# schematic.net
KiCad netlist of a schematic drawn in EasyEDA
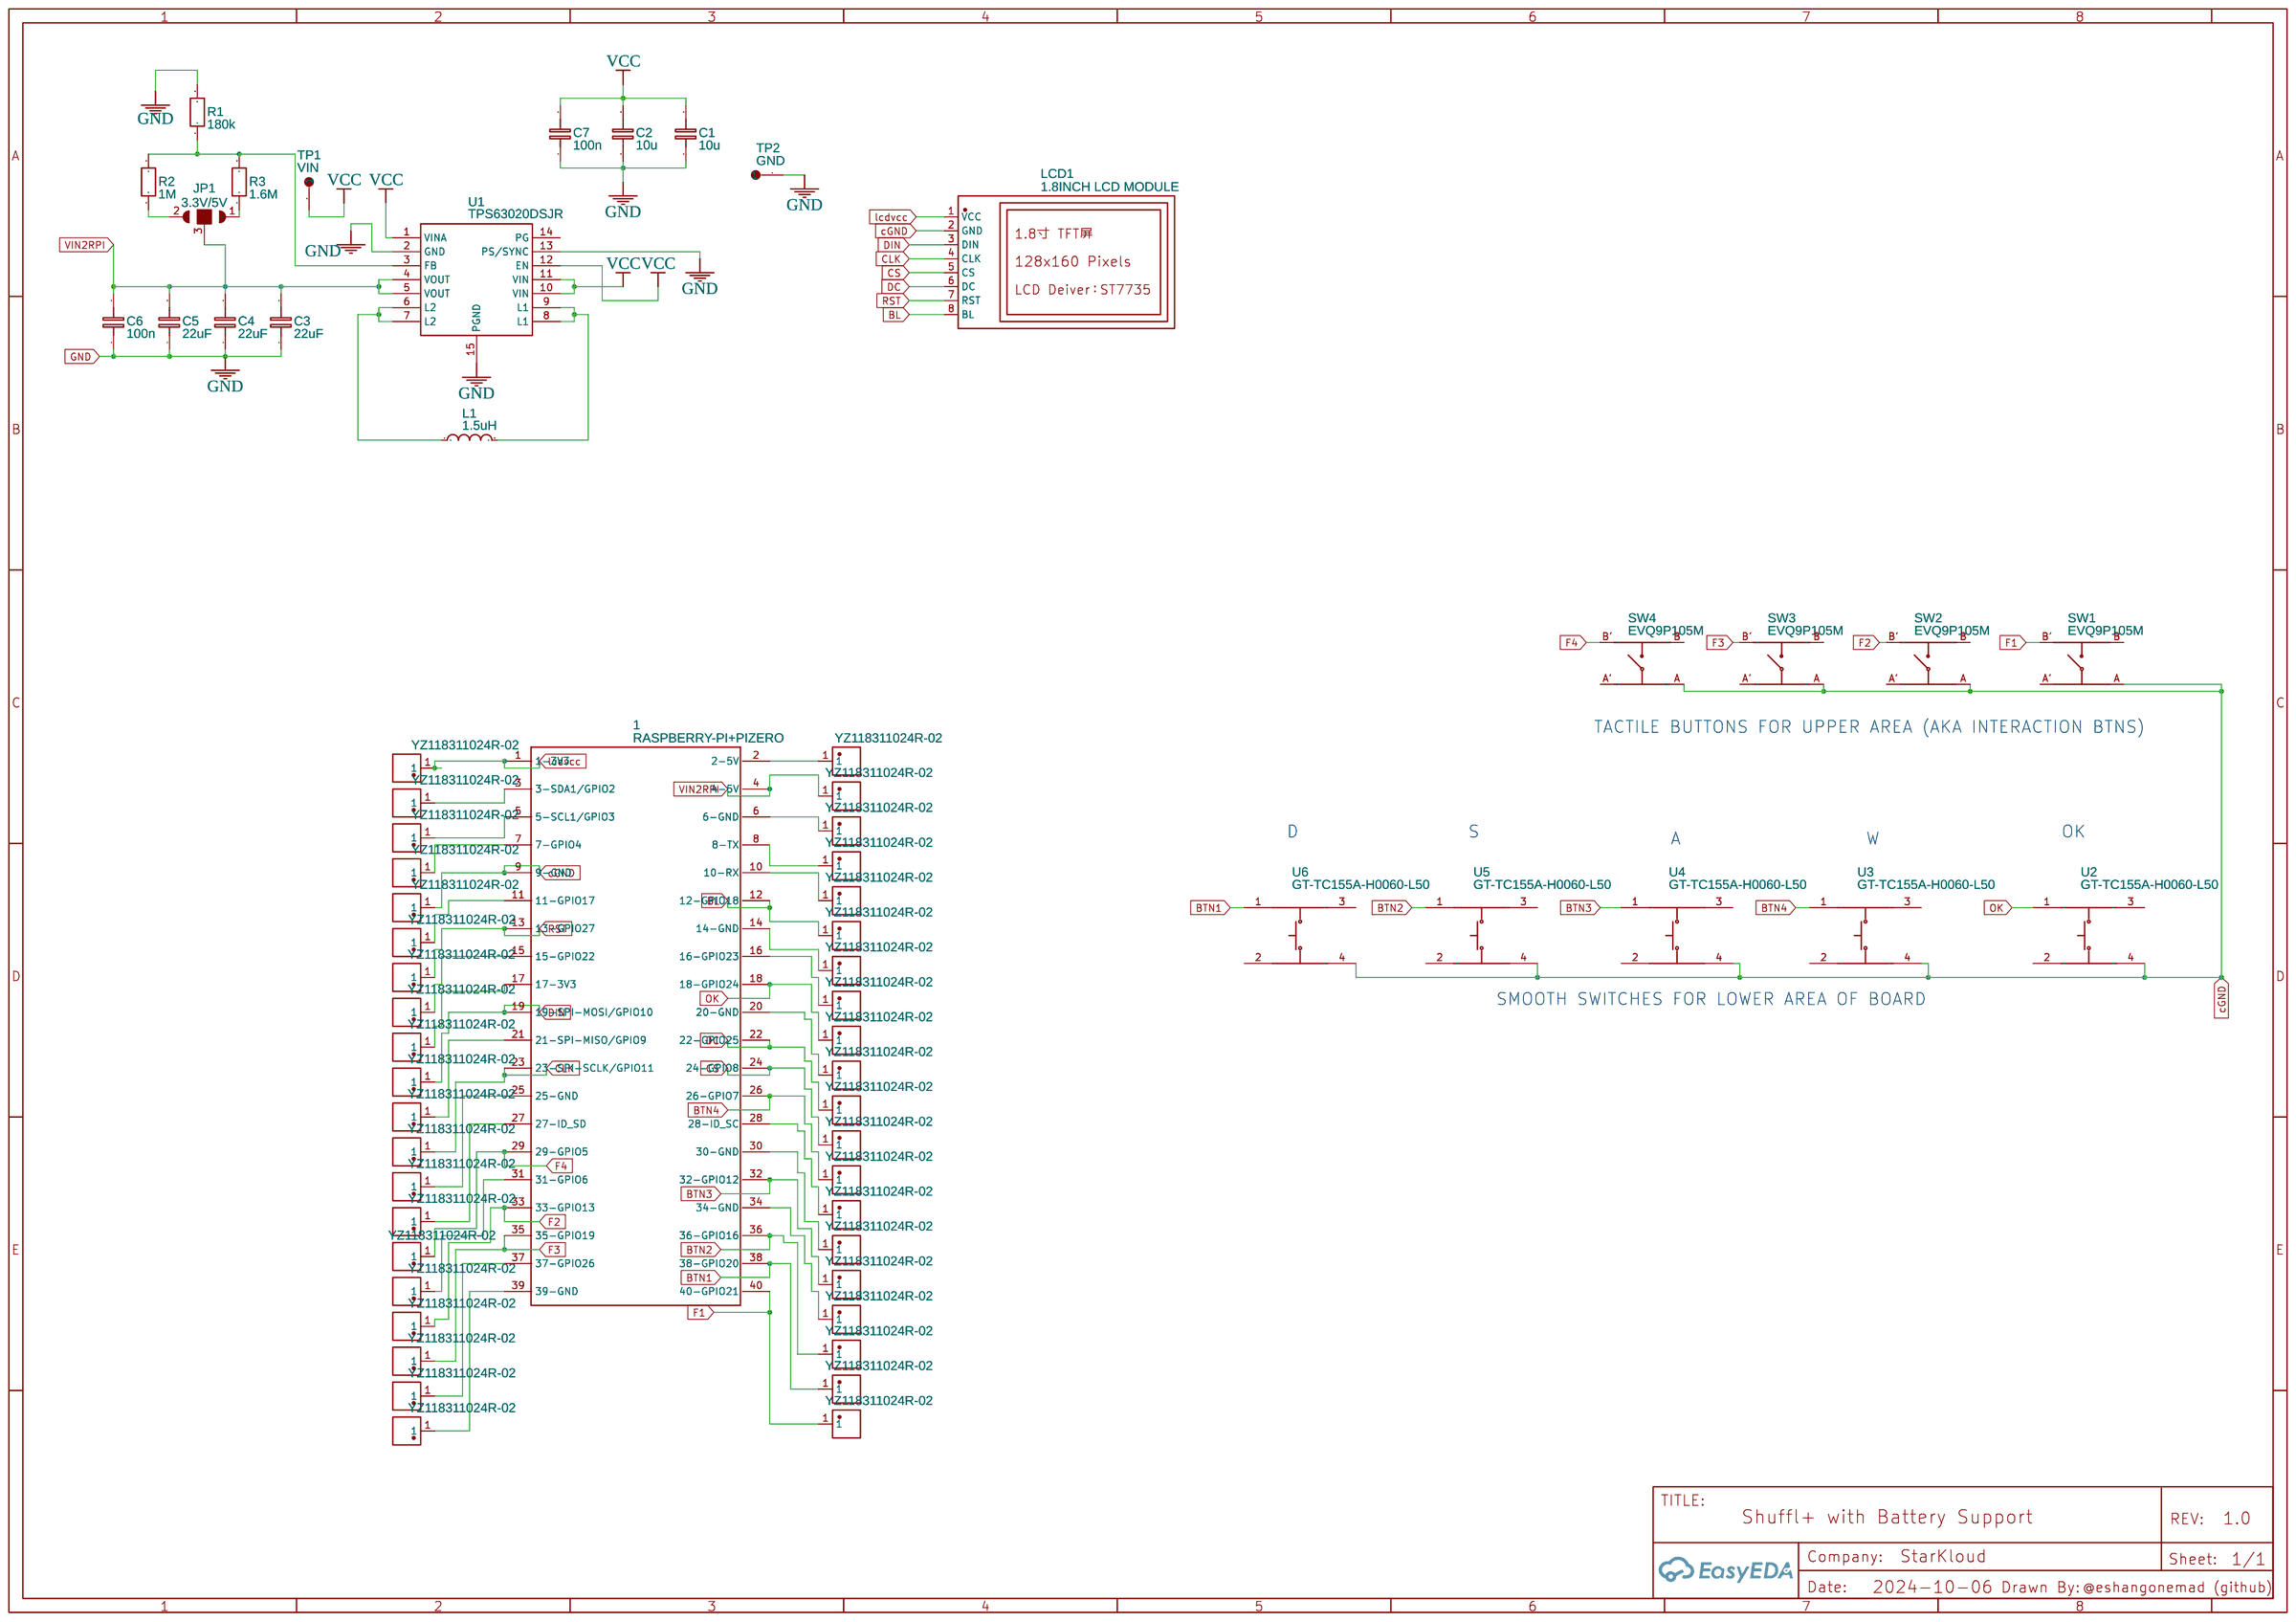
[diagram p0: schematic sheet]

(export (version "E")
  (design (tool "Eeschema 10.0.6"))
  (components
    (comp (ref "1") (value "RASPBERRY-PI+PIZERO") (libsource (lib "") (part "RASPBERRY-PI+PIZERO")))
    (comp (ref "2")
      (value "YZ118311024R-02")
      (fields (field (name "Manufacturer") "Xinyangze(鑫扬泽)"))
      (libsource (lib "") (part "YZ118311024R-02"))
    )
    (comp (ref "3")
      (value "YZ118311024R-02")
      (fields (field (name "Manufacturer") "Xinyangze(鑫扬泽)"))
      (libsource (lib "") (part "YZ118311024R-02_1"))
    )
    (comp (ref "4")
      (value "YZ118311024R-02")
      (fields (field (name "Manufacturer") "Xinyangze(鑫扬泽)"))
      (libsource (lib "") (part "YZ118311024R-02"))
    )
    (comp (ref "5")
      (value "YZ118311024R-02")
      (fields (field (name "Manufacturer") "Xinyangze(鑫扬泽)"))
      (libsource (lib "") (part "YZ118311024R-02_1"))
    )
    (comp (ref "6")
      (value "YZ118311024R-02")
      (fields (field (name "Manufacturer") "Xinyangze(鑫扬泽)"))
      (libsource (lib "") (part "YZ118311024R-02"))
    )
    (comp (ref "7")
      (value "YZ118311024R-02")
      (fields (field (name "Manufacturer") "Xinyangze(鑫扬泽)"))
      (libsource (lib "") (part "YZ118311024R-02_1"))
    )
    (comp (ref "8")
      (value "YZ118311024R-02")
      (fields (field (name "Manufacturer") "Xinyangze(鑫扬泽)"))
      (libsource (lib "") (part "YZ118311024R-02"))
    )
    (comp (ref "9")
      (value "YZ118311024R-02")
      (fields (field (name "Manufacturer") "Xinyangze(鑫扬泽)"))
      (libsource (lib "") (part "YZ118311024R-02_1"))
    )
    (comp (ref "10")
      (value "YZ118311024R-02")
      (fields (field (name "Manufacturer") "Xinyangze(鑫扬泽)"))
      (libsource (lib "") (part "YZ118311024R-02"))
    )
    (comp (ref "11")
      (value "YZ118311024R-02")
      (fields (field (name "Manufacturer") "Xinyangze(鑫扬泽)"))
      (libsource (lib "") (part "YZ118311024R-02_1"))
    )
    (comp (ref "12")
      (value "YZ118311024R-02")
      (fields (field (name "Manufacturer") "Xinyangze(鑫扬泽)"))
      (libsource (lib "") (part "YZ118311024R-02"))
    )
    (comp (ref "13")
      (value "YZ118311024R-02")
      (fields (field (name "Manufacturer") "Xinyangze(鑫扬泽)"))
      (libsource (lib "") (part "YZ118311024R-02_1"))
    )
    (comp (ref "14")
      (value "YZ118311024R-02")
      (fields (field (name "Manufacturer") "Xinyangze(鑫扬泽)"))
      (libsource (lib "") (part "YZ118311024R-02"))
    )
    (comp (ref "15")
      (value "YZ118311024R-02")
      (fields (field (name "Manufacturer") "Xinyangze(鑫扬泽)"))
      (libsource (lib "") (part "YZ118311024R-02_1"))
    )
    (comp (ref "16")
      (value "YZ118311024R-02")
      (fields (field (name "Manufacturer") "Xinyangze(鑫扬泽)"))
      (libsource (lib "") (part "YZ118311024R-02"))
    )
    (comp (ref "17")
      (value "YZ118311024R-02")
      (fields (field (name "Manufacturer") "Xinyangze(鑫扬泽)"))
      (libsource (lib "") (part "YZ118311024R-02_1"))
    )
    (comp (ref "18")
      (value "YZ118311024R-02")
      (fields (field (name "Manufacturer") "Xinyangze(鑫扬泽)"))
      (libsource (lib "") (part "YZ118311024R-02"))
    )
    (comp (ref "19")
      (value "YZ118311024R-02")
      (fields (field (name "Manufacturer") "Xinyangze(鑫扬泽)"))
      (libsource (lib "") (part "YZ118311024R-02_1"))
    )
    (comp (ref "20")
      (value "YZ118311024R-02")
      (fields (field (name "Manufacturer") "Xinyangze(鑫扬泽)"))
      (libsource (lib "") (part "YZ118311024R-02"))
    )
    (comp (ref "21")
      (value "YZ118311024R-02")
      (fields (field (name "Manufacturer") "Xinyangze(鑫扬泽)"))
      (libsource (lib "") (part "YZ118311024R-02_1"))
    )
    (comp (ref "22")
      (value "YZ118311024R-02")
      (fields (field (name "Manufacturer") "Xinyangze(鑫扬泽)"))
      (libsource (lib "") (part "YZ118311024R-02"))
    )
    (comp (ref "23")
      (value "YZ118311024R-02")
      (fields (field (name "Manufacturer") "Xinyangze(鑫扬泽)"))
      (libsource (lib "") (part "YZ118311024R-02_1"))
    )
    (comp (ref "24")
      (value "YZ118311024R-02")
      (fields (field (name "Manufacturer") "Xinyangze(鑫扬泽)"))
      (libsource (lib "") (part "YZ118311024R-02"))
    )
    (comp (ref "25")
      (value "YZ118311024R-02")
      (fields (field (name "Manufacturer") "Xinyangze(鑫扬泽)"))
      (libsource (lib "") (part "YZ118311024R-02_1"))
    )
    (comp (ref "26")
      (value "YZ118311024R-02")
      (fields (field (name "Manufacturer") "Xinyangze(鑫扬泽)"))
      (libsource (lib "") (part "YZ118311024R-02"))
    )
    (comp (ref "27")
      (value "YZ118311024R-02")
      (fields (field (name "Manufacturer") "Xinyangze(鑫扬泽)"))
      (libsource (lib "") (part "YZ118311024R-02_1"))
    )
    (comp (ref "28")
      (value "YZ118311024R-02")
      (fields (field (name "Manufacturer") "Xinyangze(鑫扬泽)"))
      (libsource (lib "") (part "YZ118311024R-02"))
    )
    (comp (ref "29")
      (value "YZ118311024R-02")
      (fields (field (name "Manufacturer") "Xinyangze(鑫扬泽)"))
      (libsource (lib "") (part "YZ118311024R-02_1"))
    )
    (comp (ref "30")
      (value "YZ118311024R-02")
      (fields (field (name "Manufacturer") "Xinyangze(鑫扬泽)"))
      (libsource (lib "") (part "YZ118311024R-02"))
    )
    (comp (ref "31")
      (value "YZ118311024R-02")
      (fields (field (name "Manufacturer") "Xinyangze(鑫扬泽)"))
      (libsource (lib "") (part "YZ118311024R-02_1"))
    )
    (comp (ref "32")
      (value "YZ118311024R-02")
      (fields (field (name "Manufacturer") "Xinyangze(鑫扬泽)"))
      (libsource (lib "") (part "YZ118311024R-02"))
    )
    (comp (ref "33")
      (value "YZ118311024R-02")
      (fields (field (name "Manufacturer") "Xinyangze(鑫扬泽)"))
      (libsource (lib "") (part "YZ118311024R-02_1"))
    )
    (comp (ref "34")
      (value "YZ118311024R-02")
      (fields (field (name "Manufacturer") "Xinyangze(鑫扬泽)"))
      (libsource (lib "") (part "YZ118311024R-02"))
    )
    (comp (ref "35")
      (value "YZ118311024R-02")
      (fields (field (name "Manufacturer") "Xinyangze(鑫扬泽)"))
      (libsource (lib "") (part "YZ118311024R-02_1"))
    )
    (comp (ref "36")
      (value "YZ118311024R-02")
      (fields (field (name "Manufacturer") "Xinyangze(鑫扬泽)"))
      (libsource (lib "") (part "YZ118311024R-02"))
    )
    (comp (ref "37")
      (value "YZ118311024R-02")
      (fields (field (name "Manufacturer") "Xinyangze(鑫扬泽)"))
      (libsource (lib "") (part "YZ118311024R-02_1"))
    )
    (comp (ref "38")
      (value "YZ118311024R-02")
      (fields (field (name "Manufacturer") "Xinyangze(鑫扬泽)"))
      (libsource (lib "") (part "YZ118311024R-02"))
    )
    (comp (ref "39")
      (value "YZ118311024R-02")
      (fields (field (name "Manufacturer") "Xinyangze(鑫扬泽)"))
      (libsource (lib "") (part "YZ118311024R-02_1"))
    )
    (comp (ref "40")
      (value "YZ118311024R-02")
      (fields (field (name "Manufacturer") "Xinyangze(鑫扬泽)"))
      (libsource (lib "") (part "YZ118311024R-02"))
    )
    (comp (ref "C1") (value "10u") (libsource (lib "") (part "C_0805_EU")))
    (comp (ref "C2") (value "10u") (libsource (lib "") (part "C_0805_EU")))
    (comp (ref "C3") (value "22uF") (libsource (lib "") (part "C_0805_EU")))
    (comp (ref "C4") (value "22uF") (libsource (lib "") (part "C_0805_EU")))
    (comp (ref "C5") (value "22uF") (libsource (lib "") (part "C_0805_EU_1")))
    (comp (ref "C6") (value "100n") (libsource (lib "") (part "C_0805_EU_1")))
    (comp (ref "C7") (value "100n") (libsource (lib "") (part "C_0805_EU")))
    (comp (ref "GP1")
      (value "YZ118311024R-02")
      (fields (field (name "Manufacturer") "Xinyangze(鑫扬泽)"))
      (libsource (lib "") (part "YZ118311024R-02_2"))
    )
    (comp (ref "JP1") (value "3.3V/5V") (libsource (lib "") (part "SOLDER BRIDGE")))
    (comp (ref "L1")
      (value "1.5uH")
      (fields
        (field (name "Manufacturer Part") "ASPIAIG-F4020-R56M-T")
        (field (name "Manufacturer") "ABRACON")
      )
      (libsource (lib "") (part "ASPIAIG-F4020-R56M-T"))
    )
    (comp (ref "LCD1")
      (value "1.8INCH LCD MODULE")
      (fields
        (field (name "Manufacturer Part") "1.8inch LCD Module")
        (field (name "Manufacturer") "Waveshare(微雪电子)")
      )
      (libsource (lib "") (part "1.8INCH LCD MODULE"))
    )
    (comp (ref "R1") (value "180k") (libsource (lib "") (part "R_0805_EU")))
    (comp (ref "R2") (value "1M") (libsource (lib "") (part "R_0805_EU")))
    (comp (ref "R3") (value "1.6M") (libsource (lib "") (part "R_0805_EU")))
    (comp (ref "SW1")
      (value "EVQ9P105M")
      (fields (field (name "Manufacturer") "PANASONIC(松下)"))
      (libsource (lib "") (part "EVQ9P105M"))
    )
    (comp (ref "SW2")
      (value "EVQ9P105M")
      (fields (field (name "Manufacturer") "PANASONIC(松下)"))
      (libsource (lib "") (part "EVQ9P105M"))
    )
    (comp (ref "SW3")
      (value "EVQ9P105M")
      (fields (field (name "Manufacturer") "PANASONIC(松下)"))
      (libsource (lib "") (part "EVQ9P105M"))
    )
    (comp (ref "SW4")
      (value "EVQ9P105M")
      (fields (field (name "Manufacturer") "PANASONIC(松下)"))
      (libsource (lib "") (part "EVQ9P105M"))
    )
    (comp (ref "TP1") (value "VIN") (libsource (lib "") (part "TEST-POINT-PTH-1X1_1")))
    (comp (ref "TP2") (value "GND") (libsource (lib "") (part "TEST-POINT-PTH-1X1")))
    (comp (ref "U1")
      (value "TPS63020DSJR")
      (fields (field (name "Manufacturer") "TI(德州仪器)"))
      (libsource (lib "") (part "TPS63020DSJR"))
    )
    (comp (ref "U2")
      (value "GT-TC155A-H0060-L50")
      (fields (field (name "Manufacturer") "G-Switch(品赞)"))
      (libsource (lib "") (part "GT-TC155A-H0060-L50"))
    )
    (comp (ref "U3")
      (value "GT-TC155A-H0060-L50")
      (fields (field (name "Manufacturer") "G-Switch(品赞)"))
      (libsource (lib "") (part "GT-TC155A-H0060-L50"))
    )
    (comp (ref "U4")
      (value "GT-TC155A-H0060-L50")
      (fields (field (name "Manufacturer") "G-Switch(品赞)"))
      (libsource (lib "") (part "GT-TC155A-H0060-L50"))
    )
    (comp (ref "U5")
      (value "GT-TC155A-H0060-L50")
      (fields (field (name "Manufacturer") "G-Switch(品赞)"))
      (libsource (lib "") (part "GT-TC155A-H0060-L50"))
    )
    (comp (ref "U6")
      (value "GT-TC155A-H0060-L50")
      (fields (field (name "Manufacturer") "G-Switch(品赞)"))
      (libsource (lib "") (part "GT-TC155A-H0060-L50"))
    )
  )
  (nets
    (net (code "1") (name "BL") (class "Default")
      (node (ref "1") (pin "12") (pinfunction "12-GPIO18_12") (pintype "bidirectional"))
      (node (ref "12") (pin "1") (pinfunction "1_1") (pintype "unspecified"))
      (node (ref "LCD1") (pin "8") (pinfunction "BL_8") (pintype "unspecified"))
    )
    (net (code "2") (name "BTN1") (class "Default")
      (node (ref "1") (pin "38") (pinfunction "38-GPIO20_38") (pintype "bidirectional"))
      (node (ref "38") (pin "1") (pinfunction "1_1") (pintype "unspecified"))
      (node (ref "U6") (pin "1") (pinfunction "1_1") (pintype "unspecified"))
    )
    (net (code "3") (name "BTN2") (class "Default")
      (node (ref "1") (pin "36") (pinfunction "36-GPIO16_36") (pintype "bidirectional"))
      (node (ref "36") (pin "1") (pinfunction "1_1") (pintype "unspecified"))
      (node (ref "U5") (pin "1") (pinfunction "1_1") (pintype "unspecified"))
    )
    (net (code "4") (name "BTN3") (class "Default")
      (node (ref "1") (pin "32") (pinfunction "32-GPIO12_32") (pintype "bidirectional"))
      (node (ref "32") (pin "1") (pinfunction "1_1") (pintype "unspecified"))
      (node (ref "U4") (pin "1") (pinfunction "1_1") (pintype "unspecified"))
    )
    (net (code "5") (name "BTN4") (class "Default")
      (node (ref "1") (pin "26") (pinfunction "26-GPIO7_26") (pintype "bidirectional"))
      (node (ref "26") (pin "1") (pinfunction "1_1") (pintype "unspecified"))
      (node (ref "U3") (pin "1") (pinfunction "1_1") (pintype "unspecified"))
    )
    (net (code "6") (name "CLK") (class "Default")
      (node (ref "1") (pin "23") (pinfunction "23-SPI-SCLK/GPIO11_23") (pintype "bidirectional"))
      (node (ref "23") (pin "1") (pinfunction "1_1") (pintype "unspecified"))
      (node (ref "LCD1") (pin "4") (pinfunction "CLK_4") (pintype "unspecified"))
    )
    (net (code "7") (name "CS") (class "Default")
      (node (ref "1") (pin "24") (pinfunction "24-GPIO8_24") (pintype "bidirectional"))
      (node (ref "24") (pin "1") (pinfunction "1_1") (pintype "unspecified"))
      (node (ref "LCD1") (pin "5") (pinfunction "CS_5") (pintype "unspecified"))
    )
    (net (code "8") (name "DC") (class "Default")
      (node (ref "1") (pin "22") (pinfunction "22-GPIO25_22") (pintype "bidirectional"))
      (node (ref "22") (pin "1") (pinfunction "1_1") (pintype "unspecified"))
      (node (ref "LCD1") (pin "6") (pinfunction "DC_6") (pintype "unspecified"))
    )
    (net (code "9") (name "DIN") (class "Default")
      (node (ref "1") (pin "19") (pinfunction "19-SPI-MOSI/GPIO10_19") (pintype "bidirectional"))
      (node (ref "19") (pin "1") (pinfunction "1_1") (pintype "unspecified"))
      (node (ref "LCD1") (pin "3") (pinfunction "DIN_3") (pintype "unspecified"))
    )
    (net (code "10") (name "F1") (class "Default")
      (node (ref "1") (pin "40") (pinfunction "40-GPIO21_40") (pintype "bidirectional"))
      (node (ref "40") (pin "1") (pinfunction "1_1") (pintype "unspecified"))
      (node (ref "SW1") (pin "B'") (pinfunction "B&apos;_B'") (pintype "unspecified"))
    )
    (net (code "11") (name "F2") (class "Default")
      (node (ref "1") (pin "33") (pinfunction "33-GPIO13_33") (pintype "bidirectional"))
      (node (ref "33") (pin "1") (pinfunction "1_1") (pintype "unspecified"))
      (node (ref "SW2") (pin "B'") (pinfunction "B&apos;_B'") (pintype "unspecified"))
    )
    (net (code "12") (name "F3") (class "Default")
      (node (ref "1") (pin "35") (pinfunction "35-GPIO19_35") (pintype "bidirectional"))
      (node (ref "35") (pin "1") (pinfunction "1_1") (pintype "unspecified"))
      (node (ref "SW3") (pin "B'") (pinfunction "B&apos;_B'") (pintype "unspecified"))
    )
    (net (code "13") (name "F4") (class "Default")
      (node (ref "1") (pin "29") (pinfunction "29-GPIO5_29") (pintype "bidirectional"))
      (node (ref "29") (pin "1") (pinfunction "1_1") (pintype "unspecified"))
      (node (ref "SW4") (pin "B'") (pinfunction "B&apos;_B'") (pintype "unspecified"))
    )
    (net (code "14") (name "GND") (class "Default")
      (node (ref "C1") (pin "1") (pinfunction "1_1") (pintype "unspecified"))
      (node (ref "C2") (pin "1") (pinfunction "1_1") (pintype "unspecified"))
      (node (ref "C3") (pin "1") (pinfunction "1_1") (pintype "unspecified"))
      (node (ref "C4") (pin "1") (pinfunction "1_1") (pintype "unspecified"))
      (node (ref "C5") (pin "1") (pinfunction "1_1") (pintype "unspecified"))
      (node (ref "C6") (pin "1") (pinfunction "1_1") (pintype "unspecified"))
      (node (ref "C7") (pin "1") (pinfunction "1_1") (pintype "unspecified"))
      (node (ref "R1") (pin "2") (pinfunction "2_2") (pintype "unspecified"))
      (node (ref "TP2") (pin "1") (pinfunction "1_1") (pintype "unspecified"))
      (node (ref "U1") (pin "13") (pinfunction "PS/SYNC_13") (pintype "unspecified"))
      (node (ref "U1") (pin "15") (pinfunction "PGND_15") (pintype "unspecified"))
      (node (ref "U1") (pin "2") (pinfunction "GND_2") (pintype "unspecified"))
    )
    (net (code "15") (name "Net-(1-2-5V)") (class "Default")
      (node (ref "1") (pin "2") (pinfunction "2-5V_2") (pintype "bidirectional"))
      (node (ref "2") (pin "1") (pinfunction "1_1") (pintype "unspecified"))
    )
    (net (code "16") (name "Net-(1-3-SDA1{slash}GPIO2)") (class "Default")
      (node (ref "1") (pin "3") (pinfunction "3-SDA1/GPIO2_3") (pintype "bidirectional"))
      (node (ref "3") (pin "1") (pinfunction "1_1") (pintype "unspecified"))
    )
    (net (code "17") (name "Net-(1-5-SCL1{slash}GPIO3)") (class "Default")
      (node (ref "1") (pin "5") (pinfunction "5-SCL1/GPIO3_5") (pintype "bidirectional"))
      (node (ref "5") (pin "1") (pinfunction "1_1") (pintype "unspecified"))
    )
    (net (code "18") (name "Net-(1-6-GND)") (class "Default")
      (node (ref "1") (pin "6") (pinfunction "6-GND_6") (pintype "bidirectional"))
      (node (ref "6") (pin "1") (pinfunction "1_1") (pintype "unspecified"))
    )
    (net (code "19") (name "Net-(1-7-GPIO4)") (class "Default")
      (node (ref "1") (pin "7") (pinfunction "7-GPIO4_7") (pintype "bidirectional"))
      (node (ref "7") (pin "1") (pinfunction "1_1") (pintype "unspecified"))
    )
    (net (code "20") (name "Net-(1-8-TX)") (class "Default")
      (node (ref "1") (pin "8") (pinfunction "8-TX_8") (pintype "bidirectional"))
      (node (ref "8") (pin "1") (pinfunction "1_1") (pintype "unspecified"))
    )
    (net (code "21") (name "Net-(1-10-RX)") (class "Default")
      (node (ref "1") (pin "10") (pinfunction "10-RX_10") (pintype "bidirectional"))
      (node (ref "10") (pin "1") (pinfunction "1_1") (pintype "unspecified"))
    )
    (net (code "22") (name "Net-(1-11-GPIO17)") (class "Default")
      (node (ref "1") (pin "11") (pinfunction "11-GPIO17_11") (pintype "bidirectional"))
      (node (ref "11") (pin "1") (pinfunction "1_1") (pintype "unspecified"))
    )
    (net (code "23") (name "Net-(1-14-GND)") (class "Default")
      (node (ref "1") (pin "14") (pinfunction "14-GND_14") (pintype "bidirectional"))
      (node (ref "14") (pin "1") (pinfunction "1_1") (pintype "unspecified"))
    )
    (net (code "24") (name "Net-(1-15-GPIO22)") (class "Default")
      (node (ref "1") (pin "15") (pinfunction "15-GPIO22_15") (pintype "bidirectional"))
      (node (ref "15") (pin "1") (pinfunction "1_1") (pintype "unspecified"))
    )
    (net (code "25") (name "Net-(1-16-GPIO23)") (class "Default")
      (node (ref "1") (pin "16") (pinfunction "16-GPIO23_16") (pintype "bidirectional"))
      (node (ref "16") (pin "1") (pinfunction "1_1") (pintype "unspecified"))
    )
    (net (code "26") (name "Net-(1-17-3V3)") (class "Default")
      (node (ref "1") (pin "17") (pinfunction "17-3V3_17") (pintype "bidirectional"))
      (node (ref "17") (pin "1") (pinfunction "1_1") (pintype "unspecified"))
    )
    (net (code "27") (name "Net-(1-20-GND)") (class "Default")
      (node (ref "1") (pin "20") (pinfunction "20-GND_20") (pintype "bidirectional"))
      (node (ref "20") (pin "1") (pinfunction "1_1") (pintype "unspecified"))
    )
    (net (code "28") (name "Net-(1-21-SPI-MISO{slash}GPIO9)") (class "Default")
      (node (ref "1") (pin "21") (pinfunction "21-SPI-MISO/GPIO9_21") (pintype "bidirectional"))
      (node (ref "21") (pin "1") (pinfunction "1_1") (pintype "unspecified"))
    )
    (net (code "29") (name "Net-(1-25-GND)") (class "Default")
      (node (ref "1") (pin "25") (pinfunction "25-GND_25") (pintype "bidirectional"))
      (node (ref "25") (pin "1") (pinfunction "1_1") (pintype "unspecified"))
    )
    (net (code "30") (name "Net-(1-27-ID_SD)") (class "Default")
      (node (ref "1") (pin "27") (pinfunction "27-ID_SD_27") (pintype "bidirectional"))
      (node (ref "27") (pin "1") (pinfunction "1_1") (pintype "unspecified"))
    )
    (net (code "31") (name "Net-(1-28-ID_SC)") (class "Default")
      (node (ref "1") (pin "28") (pinfunction "28-ID_SC_28") (pintype "bidirectional"))
      (node (ref "28") (pin "1") (pinfunction "1_1") (pintype "unspecified"))
    )
    (net (code "32") (name "Net-(1-30-GND)") (class "Default")
      (node (ref "1") (pin "30") (pinfunction "30-GND_30") (pintype "bidirectional"))
      (node (ref "30") (pin "1") (pinfunction "1_1") (pintype "unspecified"))
    )
    (net (code "33") (name "Net-(1-31-GPIO6)") (class "Default")
      (node (ref "1") (pin "31") (pinfunction "31-GPIO6_31") (pintype "bidirectional"))
      (node (ref "31") (pin "1") (pinfunction "1_1") (pintype "unspecified"))
    )
    (net (code "34") (name "Net-(1-34-GND)") (class "Default")
      (node (ref "1") (pin "34") (pinfunction "34-GND_34") (pintype "bidirectional"))
      (node (ref "34") (pin "1") (pinfunction "1_1") (pintype "unspecified"))
    )
    (net (code "35") (name "Net-(1-37-GPIO26)") (class "Default")
      (node (ref "1") (pin "37") (pinfunction "37-GPIO26_37") (pintype "bidirectional"))
      (node (ref "37") (pin "1") (pinfunction "1_1") (pintype "unspecified"))
    )
    (net (code "36") (name "Net-(1-39-GND)") (class "Default")
      (node (ref "1") (pin "39") (pinfunction "39-GND_39") (pintype "bidirectional"))
      (node (ref "39") (pin "1") (pinfunction "1_1") (pintype "unspecified"))
    )
    (net (code "37") (name "Net-(JP1-Pad1)") (class "Default")
      (node (ref "JP1") (pin "1") (pinfunction "1_1") (pintype "unspecified"))
      (node (ref "R3") (pin "1") (pinfunction "1_1") (pintype "unspecified"))
    )
    (net (code "38") (name "Net-(JP1-Pad2)") (class "Default")
      (node (ref "JP1") (pin "2") (pinfunction "2_2") (pintype "unspecified"))
      (node (ref "R2") (pin "1") (pinfunction "1_1") (pintype "unspecified"))
    )
    (net (code "39") (name "Net-(L1-Pad1)") (class "Default")
      (node (ref "L1") (pin "1") (pinfunction "1_1") (pintype "unspecified"))
      (node (ref "U1") (pin "6") (pinfunction "L2_6") (pintype "unspecified"))
      (node (ref "U1") (pin "7") (pinfunction "L2_7") (pintype "unspecified"))
    )
    (net (code "40") (name "Net-(L1-Pad2)") (class "Default")
      (node (ref "L1") (pin "2") (pinfunction "2_2") (pintype "unspecified"))
      (node (ref "U1") (pin "8") (pinfunction "L1_8") (pintype "unspecified"))
      (node (ref "U1") (pin "9") (pinfunction "L1_9") (pintype "unspecified"))
    )
    (net (code "41") (name "Net-(U1-FB)") (class "Default")
      (node (ref "R1") (pin "1") (pinfunction "1_1") (pintype "unspecified"))
      (node (ref "R2") (pin "2") (pinfunction "2_2") (pintype "unspecified"))
      (node (ref "R3") (pin "2") (pinfunction "2_2") (pintype "unspecified"))
      (node (ref "U1") (pin "3") (pinfunction "FB_3") (pintype "unspecified"))
    )
    (net (code "42") (name "OK") (class "Default")
      (node (ref "1") (pin "18") (pinfunction "18-GPIO24_18") (pintype "bidirectional"))
      (node (ref "18") (pin "1") (pinfunction "1_1") (pintype "unspecified"))
      (node (ref "U2") (pin "1") (pinfunction "1_1") (pintype "unspecified"))
    )
    (net (code "43") (name "RST") (class "Default")
      (node (ref "1") (pin "13") (pinfunction "13-GPIO27_13") (pintype "bidirectional"))
      (node (ref "13") (pin "1") (pinfunction "1_1") (pintype "unspecified"))
      (node (ref "LCD1") (pin "7") (pinfunction "RST_7") (pintype "unspecified"))
    )
    (net (code "44") (name "VCC") (class "Default")
      (node (ref "C1") (pin "2") (pinfunction "2_2") (pintype "unspecified"))
      (node (ref "C2") (pin "2") (pinfunction "2_2") (pintype "unspecified"))
      (node (ref "C7") (pin "2") (pinfunction "2_2") (pintype "unspecified"))
      (node (ref "TP1") (pin "1") (pinfunction "1_1") (pintype "unspecified"))
      (node (ref "U1") (pin "1") (pinfunction "VINA_1") (pintype "unspecified"))
      (node (ref "U1") (pin "10") (pinfunction "VIN_10") (pintype "unspecified"))
      (node (ref "U1") (pin "11") (pinfunction "VIN_11") (pintype "unspecified"))
      (node (ref "U1") (pin "12") (pinfunction "EN_12") (pintype "unspecified"))
    )
    (net (code "45") (name "VIN2RPI") (class "Default")
      (node (ref "1") (pin "4") (pinfunction "4-5V_4") (pintype "bidirectional"))
      (node (ref "4") (pin "1") (pinfunction "1_1") (pintype "unspecified"))
      (node (ref "C3") (pin "2") (pinfunction "2_2") (pintype "unspecified"))
      (node (ref "C4") (pin "2") (pinfunction "2_2") (pintype "unspecified"))
      (node (ref "C5") (pin "2") (pinfunction "2_2") (pintype "unspecified"))
      (node (ref "C6") (pin "2") (pinfunction "2_2") (pintype "unspecified"))
      (node (ref "JP1") (pin "3") (pinfunction "3_3") (pintype "unspecified"))
      (node (ref "U1") (pin "4") (pinfunction "VOUT_4") (pintype "unspecified"))
      (node (ref "U1") (pin "5") (pinfunction "VOUT_5") (pintype "unspecified"))
    )
    (net (code "46") (name "cGND") (class "Default")
      (node (ref "1") (pin "9") (pinfunction "9-GND_9") (pintype "bidirectional"))
      (node (ref "9") (pin "1") (pinfunction "1_1") (pintype "unspecified"))
      (node (ref "LCD1") (pin "2") (pinfunction "GND_2") (pintype "unspecified"))
      (node (ref "SW1") (pin "A") (pinfunction "A_A") (pintype "unspecified"))
      (node (ref "SW2") (pin "A") (pinfunction "A_A") (pintype "unspecified"))
      (node (ref "SW3") (pin "A") (pinfunction "A_A") (pintype "unspecified"))
      (node (ref "SW4") (pin "A") (pinfunction "A_A") (pintype "unspecified"))
      (node (ref "U2") (pin "4") (pinfunction "4_4") (pintype "unspecified"))
      (node (ref "U3") (pin "4") (pinfunction "4_4") (pintype "unspecified"))
      (node (ref "U4") (pin "4") (pinfunction "4_4") (pintype "unspecified"))
      (node (ref "U5") (pin "4") (pinfunction "4_4") (pintype "unspecified"))
      (node (ref "U6") (pin "4") (pinfunction "4_4") (pintype "unspecified"))
    )
    (net (code "47") (name "lcdvcc") (class "Default")
      (node (ref "1") (pin "1") (pinfunction "1-3V3_1") (pintype "bidirectional"))
      (node (ref "GP1") (pin "1") (pinfunction "1_1") (pintype "unspecified"))
      (node (ref "LCD1") (pin "1") (pinfunction "VCC_1") (pintype "unspecified"))
    )
    (net (code "48") (name "unconnected-(SW1-A&apos;-PadA')") (class "Default")
      (node (ref "SW1") (pin "A'") (pinfunction "A&apos;_A'") (pintype "unspecified"))
    )
    (net (code "49") (name "unconnected-(SW1-PadB)") (class "Default")
      (node (ref "SW1") (pin "B") (pinfunction "B_B") (pintype "unspecified"))
    )
    (net (code "50") (name "unconnected-(SW2-A&apos;-PadA')") (class "Default")
      (node (ref "SW2") (pin "A'") (pinfunction "A&apos;_A'") (pintype "unspecified"))
    )
    (net (code "51") (name "unconnected-(SW2-PadB)") (class "Default")
      (node (ref "SW2") (pin "B") (pinfunction "B_B") (pintype "unspecified"))
    )
    (net (code "52") (name "unconnected-(SW3-A&apos;-PadA')") (class "Default")
      (node (ref "SW3") (pin "A'") (pinfunction "A&apos;_A'") (pintype "unspecified"))
    )
    (net (code "53") (name "unconnected-(SW3-PadB)") (class "Default")
      (node (ref "SW3") (pin "B") (pinfunction "B_B") (pintype "unspecified"))
    )
    (net (code "54") (name "unconnected-(SW4-A&apos;-PadA')") (class "Default")
      (node (ref "SW4") (pin "A'") (pinfunction "A&apos;_A'") (pintype "unspecified"))
    )
    (net (code "55") (name "unconnected-(SW4-PadB)") (class "Default")
      (node (ref "SW4") (pin "B") (pinfunction "B_B") (pintype "unspecified"))
    )
    (net (code "56") (name "unconnected-(U1-PG-Pad14)") (class "Default")
      (node (ref "U1") (pin "14") (pinfunction "PG_14") (pintype "unspecified"))
    )
    (net (code "57") (name "unconnected-(U2-Pad2)") (class "Default")
      (node (ref "U2") (pin "2") (pinfunction "2_2") (pintype "unspecified"))
    )
    (net (code "58") (name "unconnected-(U2-Pad3)") (class "Default")
      (node (ref "U2") (pin "3") (pinfunction "3_3") (pintype "unspecified"))
    )
    (net (code "59") (name "unconnected-(U3-Pad2)") (class "Default")
      (node (ref "U3") (pin "2") (pinfunction "2_2") (pintype "unspecified"))
    )
    (net (code "60") (name "unconnected-(U3-Pad3)") (class "Default")
      (node (ref "U3") (pin "3") (pinfunction "3_3") (pintype "unspecified"))
    )
    (net (code "61") (name "unconnected-(U4-Pad2)") (class "Default")
      (node (ref "U4") (pin "2") (pinfunction "2_2") (pintype "unspecified"))
    )
    (net (code "62") (name "unconnected-(U4-Pad3)") (class "Default")
      (node (ref "U4") (pin "3") (pinfunction "3_3") (pintype "unspecified"))
    )
    (net (code "63") (name "unconnected-(U5-Pad2)") (class "Default")
      (node (ref "U5") (pin "2") (pinfunction "2_2") (pintype "unspecified"))
    )
    (net (code "64") (name "unconnected-(U5-Pad3)") (class "Default")
      (node (ref "U5") (pin "3") (pinfunction "3_3") (pintype "unspecified"))
    )
    (net (code "65") (name "unconnected-(U6-Pad2)") (class "Default")
      (node (ref "U6") (pin "2") (pinfunction "2_2") (pintype "unspecified"))
    )
    (net (code "66") (name "unconnected-(U6-Pad3)") (class "Default")
      (node (ref "U6") (pin "3") (pinfunction "3_3") (pintype "unspecified"))
    )
  )
)
